# StepStick-Protector_v10.net
KiCad netlist of a schematic drawn in EAGLE
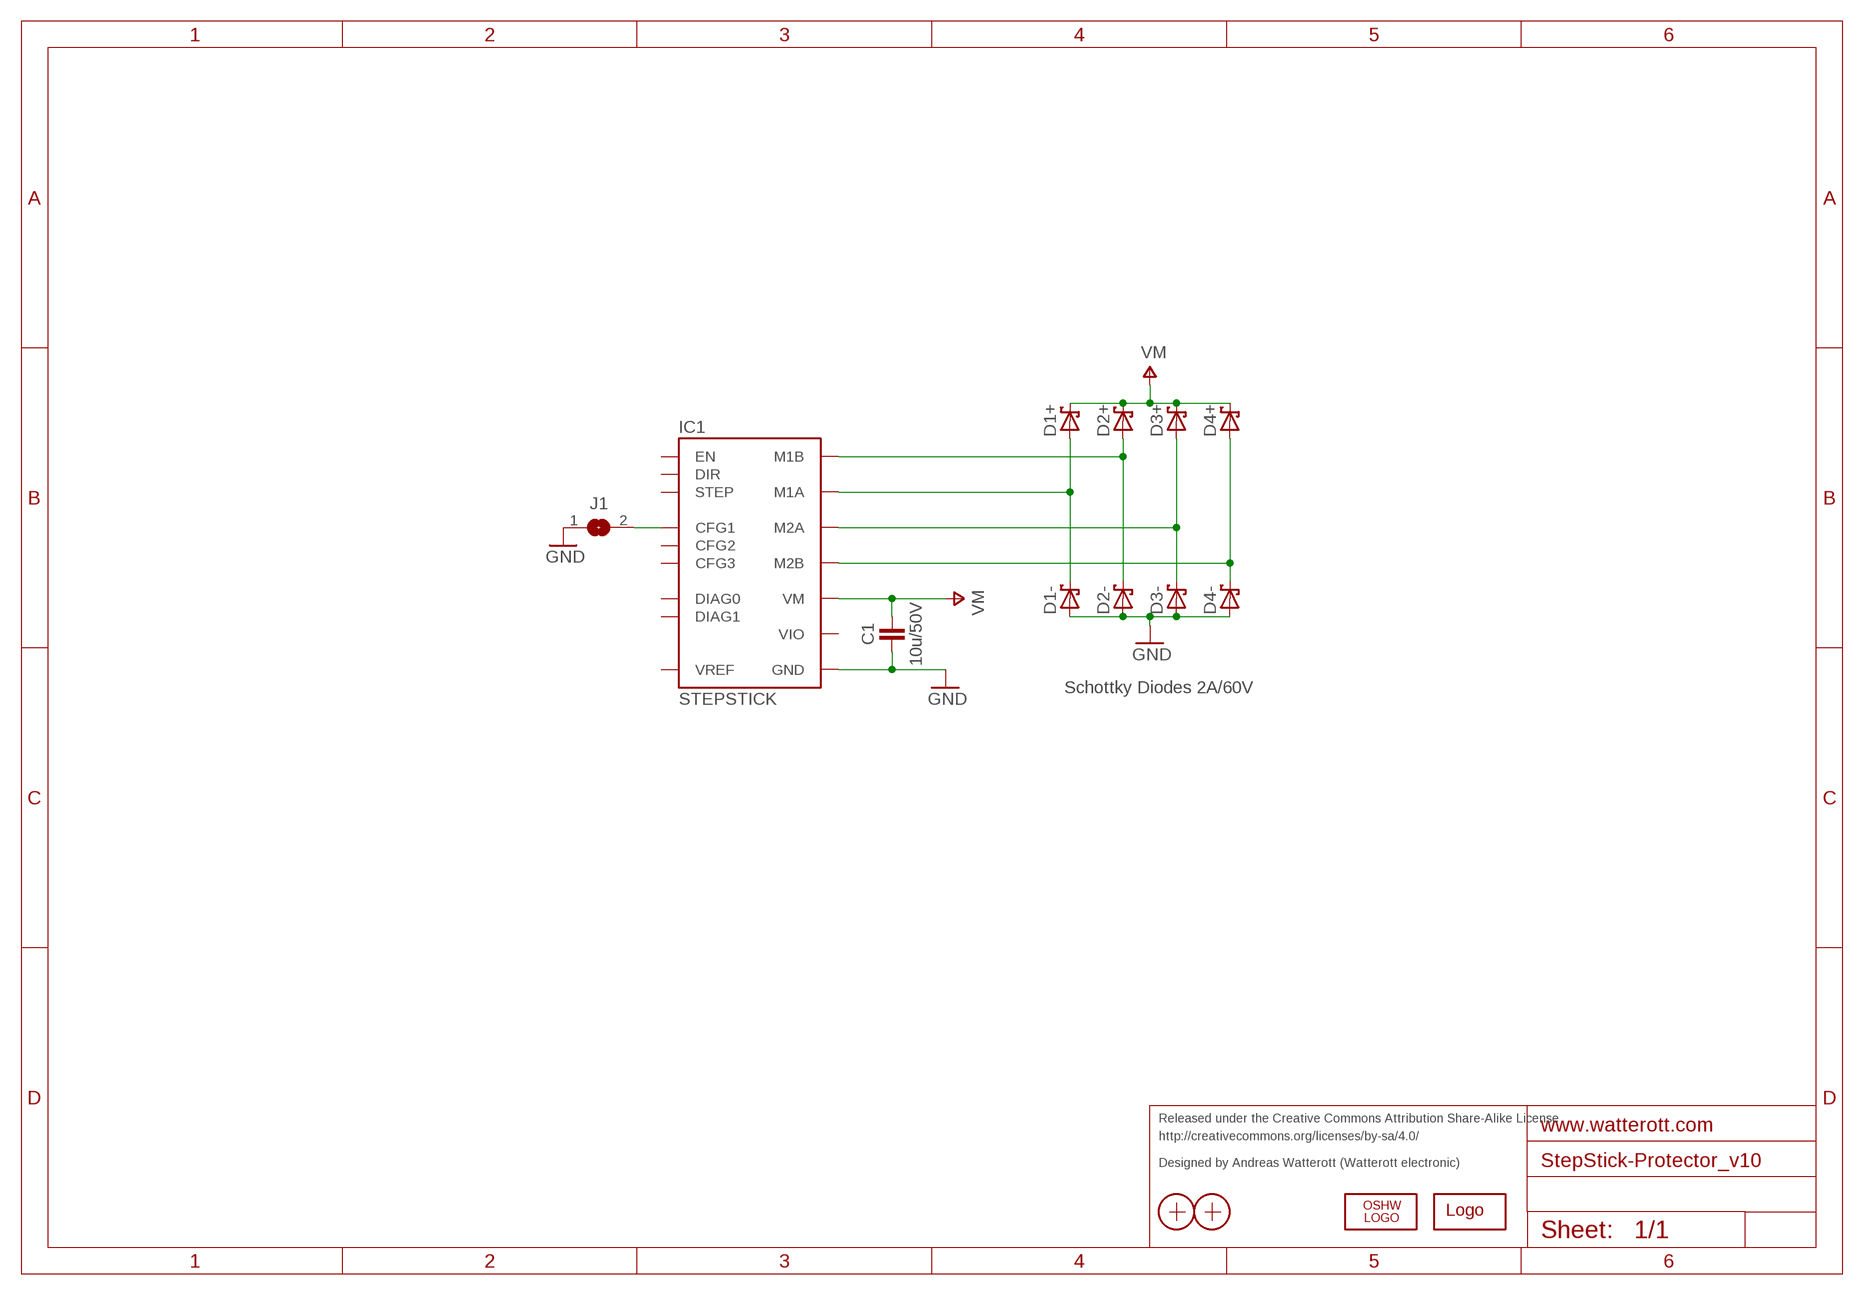
[diagram p0: schematic, sheet 1]

(export (version "E")
  (design (tool "Eeschema 10.0.6"))
  (components
    (comp (ref "C1")
      (value "10u/50V")
      (footprint "eagle-import:C1210")
      (libsource (lib "eagle-import") (part "CAPACITOR-1210"))
    )
    (comp (ref "D1+")
      (value "D_SCHOTTKY-SS14")
      (footprint "eagle-import:SMA_DO214AC")
      (libsource (lib "eagle-import") (part "D_SCHOTTKY-SS14"))
    )
    (comp (ref "D1-")
      (value "D_SCHOTTKY-SS14")
      (footprint "eagle-import:SMA_DO214AC")
      (libsource (lib "eagle-import") (part "D_SCHOTTKY-SS14"))
    )
    (comp (ref "D2+")
      (value "D_SCHOTTKY-SS14")
      (footprint "eagle-import:SMA_DO214AC")
      (libsource (lib "eagle-import") (part "D_SCHOTTKY-SS14"))
    )
    (comp (ref "D2-")
      (value "D_SCHOTTKY-SS14")
      (footprint "eagle-import:SMA_DO214AC")
      (libsource (lib "eagle-import") (part "D_SCHOTTKY-SS14"))
    )
    (comp (ref "D3+")
      (value "D_SCHOTTKY-SS14")
      (footprint "eagle-import:SMA_DO214AC")
      (libsource (lib "eagle-import") (part "D_SCHOTTKY-SS14"))
    )
    (comp (ref "D3-")
      (value "D_SCHOTTKY-SS14")
      (footprint "eagle-import:SMA_DO214AC")
      (libsource (lib "eagle-import") (part "D_SCHOTTKY-SS14"))
    )
    (comp (ref "D4+")
      (value "D_SCHOTTKY-SS14")
      (footprint "eagle-import:SMA_DO214AC")
      (libsource (lib "eagle-import") (part "D_SCHOTTKY-SS14"))
    )
    (comp (ref "D4-")
      (value "D_SCHOTTKY-SS14")
      (footprint "eagle-import:SMA_DO214AC")
      (libsource (lib "eagle-import") (part "D_SCHOTTKY-SS14"))
    )
    (comp (ref "IC1")
      (value "STEPSTICK")
      (footprint "eagle-import:STEPSTICK")
      (libsource (lib "eagle-import") (part "STEPSTICK"))
    )
    (comp (ref "J1")
      (value "JUMPER2-0603-NC")
      (footprint "eagle-import:JUMPER2-0603_NC")
      (libsource (lib "eagle-import") (part "JUMPER2-0603-NC"))
    )
    (comp (ref "LOGO1")
      (value "OSHW_LOGOX0070")
      (footprint "eagle-import:OSHW_6X70")
      (libsource (lib "eagle-import") (part "OSHW_LOGOX0070"))
    )
    (comp (ref "LOGO2")
      (value "LOGO-S_PLACE_S")
      (footprint "eagle-import:SPARK_TPLACE_S")
      (libsource (lib "eagle-import") (part "LOGO-S_PLACE_S"))
    )
    (comp (ref "X1")
      (value "PASSER")
      (footprint "eagle-import:PASSER")
      (libsource (lib "eagle-import") (part "PASSER"))
    )
    (comp (ref "X2")
      (value "PASSER")
      (footprint "eagle-import:PASSER")
      (libsource (lib "eagle-import") (part "PASSER"))
    )
  )
  (nets
    (net (code "1") (name "/VIO") (class "Default")
      (node (ref "IC1") (pin "VIO") (pinfunction "VIO_VIO") (pintype "power_in"))
    )
    (net (code "2") (name "GND") (class "Default")
      (node (ref "C1") (pin "1") (pinfunction "1_1") (pintype "passive"))
      (node (ref "D1-") (pin "A") (pinfunction "A_A") (pintype "passive"))
      (node (ref "D2-") (pin "A") (pinfunction "A_A") (pintype "passive"))
      (node (ref "D3-") (pin "A") (pinfunction "A_A") (pintype "passive"))
      (node (ref "D4-") (pin "A") (pinfunction "A_A") (pintype "passive"))
      (node (ref "IC1") (pin "GND@1") (pinfunction "GND_GND@1") (pintype "power_in"))
      (node (ref "IC1") (pin "GND@2") (pinfunction "GND_GND@2") (pintype "power_in"))
      (node (ref "J1") (pin "1") (pinfunction "1_1") (pintype "passive"))
    )
    (net (code "3") (name "Net-(D1+-PadA)") (class "Default")
      (node (ref "D1+") (pin "A") (pinfunction "A_A") (pintype "passive"))
      (node (ref "D1-") (pin "C") (pinfunction "C_C") (pintype "passive"))
      (node (ref "IC1") (pin "M1A") (pinfunction "M1A_M1A") (pintype "output"))
    )
    (net (code "4") (name "Net-(D2+-PadA)") (class "Default")
      (node (ref "D2+") (pin "A") (pinfunction "A_A") (pintype "passive"))
      (node (ref "D2-") (pin "C") (pinfunction "C_C") (pintype "passive"))
      (node (ref "IC1") (pin "M1B") (pinfunction "M1B_M1B") (pintype "output"))
    )
    (net (code "5") (name "Net-(D3+-PadA)") (class "Default")
      (node (ref "D3+") (pin "A") (pinfunction "A_A") (pintype "passive"))
      (node (ref "D3-") (pin "C") (pinfunction "C_C") (pintype "passive"))
      (node (ref "IC1") (pin "M2A") (pinfunction "M2A_M2A") (pintype "output"))
    )
    (net (code "6") (name "Net-(D4+-PadA)") (class "Default")
      (node (ref "D4+") (pin "A") (pinfunction "A_A") (pintype "passive"))
      (node (ref "D4-") (pin "C") (pinfunction "C_C") (pintype "passive"))
      (node (ref "IC1") (pin "M2B") (pinfunction "M2B_M2B") (pintype "output"))
    )
    (net (code "7") (name "Net-(IC1-PadCFG1)") (class "Default")
      (node (ref "IC1") (pin "CFG1") (pinfunction "CFG1_CFG1") (pintype "bidirectional"))
      (node (ref "J1") (pin "2") (pinfunction "2_2") (pintype "passive"))
    )
    (net (code "8") (name "VM") (class "Default")
      (node (ref "C1") (pin "2") (pinfunction "2_2") (pintype "passive"))
      (node (ref "D1+") (pin "C") (pinfunction "C_C") (pintype "passive"))
      (node (ref "D2+") (pin "C") (pinfunction "C_C") (pintype "passive"))
      (node (ref "D3+") (pin "C") (pinfunction "C_C") (pintype "passive"))
      (node (ref "D4+") (pin "C") (pinfunction "C_C") (pintype "passive"))
      (node (ref "IC1") (pin "VM") (pinfunction "VM_VM") (pintype "power_in"))
    )
    (net (code "9") (name "unconnected-(IC1-PadCFG2)") (class "Default")
      (node (ref "IC1") (pin "CFG2") (pinfunction "CFG2_CFG2") (pintype "bidirectional"))
    )
    (net (code "10") (name "unconnected-(IC1-PadCFG3)") (class "Default")
      (node (ref "IC1") (pin "CFG3") (pinfunction "CFG3_CFG3") (pintype "bidirectional"))
    )
    (net (code "11") (name "unconnected-(IC1-PadDIAG0)") (class "Default")
      (node (ref "IC1") (pin "DIAG0") (pinfunction "DIAG0_DIAG0") (pintype "bidirectional"))
    )
    (net (code "12") (name "unconnected-(IC1-PadDIAG1)") (class "Default")
      (node (ref "IC1") (pin "DIAG1") (pinfunction "DIAG1_DIAG1") (pintype "bidirectional"))
    )
    (net (code "13") (name "unconnected-(IC1-PadDIR)") (class "Default")
      (node (ref "IC1") (pin "DIR") (pinfunction "DIR_DIR") (pintype "bidirectional"))
    )
    (net (code "14") (name "unconnected-(IC1-PadEN)") (class "Default")
      (node (ref "IC1") (pin "EN") (pinfunction "EN_EN") (pintype "bidirectional"))
    )
    (net (code "15") (name "unconnected-(IC1-PadSTEP)") (class "Default")
      (node (ref "IC1") (pin "STEP") (pinfunction "STEP_STEP") (pintype "bidirectional"))
    )
    (net (code "16") (name "unconnected-(IC1-PadVREF)") (class "Default")
      (node (ref "IC1") (pin "VREF") (pinfunction "VREF_VREF") (pintype "passive"))
    )
  )
)
